# atmega_breakout.net
KiCad netlist of a schematic drawn in EAGLE
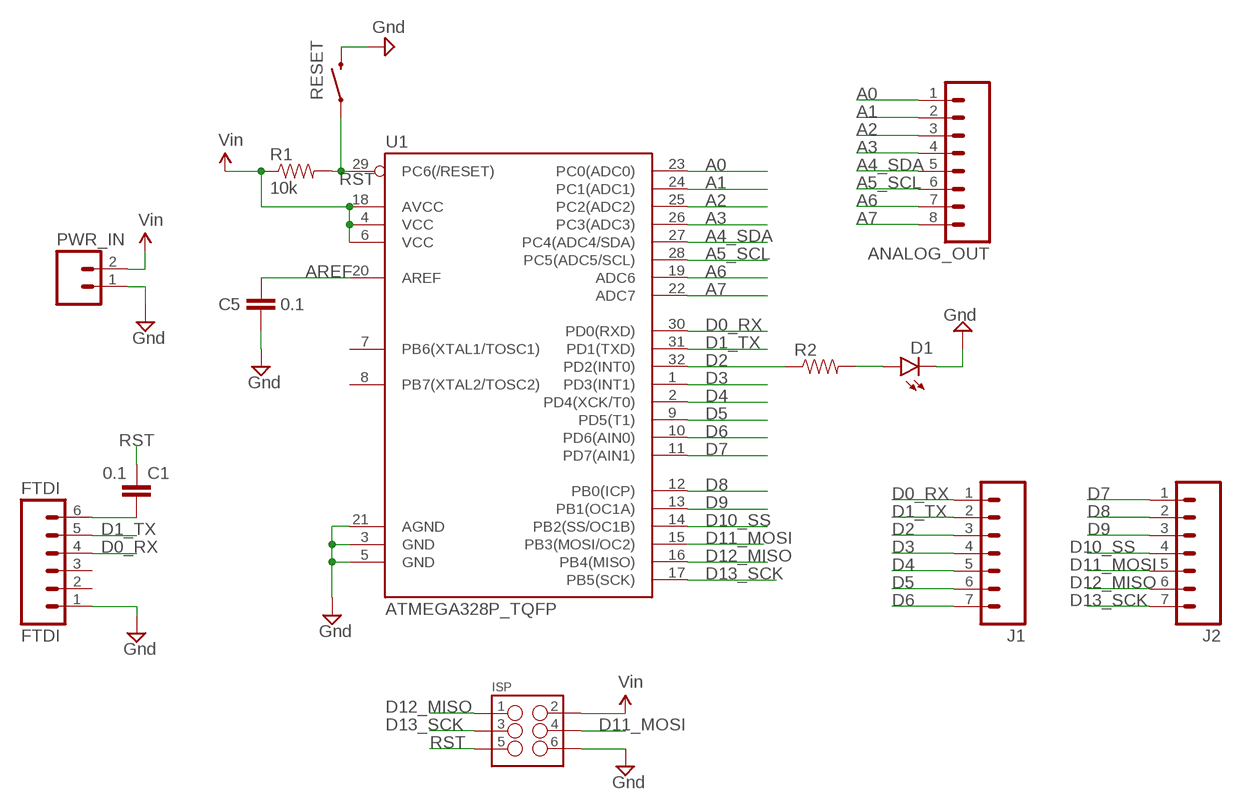
[diagram p0: schematic, sheet 1]

(export (version "E")
  (design (tool "Eeschema 10.0.6"))
  (components
    (comp (ref "ANALOG_OUT")
      (value "M08")
      (footprint "eagle-import:1X08_ROUND")
      (libsource (lib "eagle-import") (part "M08"))
    )
    (comp (ref "C1")
      (value "0.1")
      (footprint "eagle-import:1206")
      (libsource (lib "eagle-import") (part "SparkFun-Passives_CAP1206"))
    )
    (comp (ref "C5")
      (value "0.1")
      (footprint "eagle-import:1206")
      (libsource (lib "eagle-import") (part "CAP1206"))
    )
    (comp (ref "D1")
      (value "LED1206")
      (footprint "eagle-import:LED-1206")
      (libsource (lib "eagle-import") (part "LED1206"))
    )
    (comp (ref "FTDI")
      (value "FTDI")
      (footprint "eagle-import:1X06")
      (libsource (lib "eagle-import") (part "M06SIP"))
    )
    (comp (ref "ISP")
      (value "M03X22X3_SILK_MALE_PTH")
      (footprint "eagle-import:2X3")
      (libsource (lib "eagle-import") (part "M03X22X3_SILK_MALE_PTH"))
    )
    (comp (ref "J1")
      (value "M07")
      (footprint "eagle-import:1X07")
      (libsource (lib "eagle-import") (part "M07"))
    )
    (comp (ref "J2")
      (value "M07")
      (footprint "eagle-import:1X07")
      (libsource (lib "eagle-import") (part "M07"))
    )
    (comp (ref "PWR_IN")
      (value "M02PTH")
      (footprint "eagle-import:1X02")
      (libsource (lib "eagle-import") (part "M02PTH"))
    )
    (comp (ref "R1")
      (value "10k")
      (footprint "eagle-import:1206")
      (libsource (lib "eagle-import") (part "RESISTOR1206"))
    )
    (comp (ref "R2")
      (value "RESISTOR1206")
      (footprint "eagle-import:1206")
      (libsource (lib "eagle-import") (part "RESISTOR1206"))
    )
    (comp (ref "RESET")
      (value "SWITCH-MOMENTARY-2SMD")
      (footprint "eagle-import:TACTILE-SWITCH-SMD")
      (libsource (lib "eagle-import") (part "SWITCH-MOMENTARY-2SMD"))
    )
    (comp (ref "U1")
      (value "ATMEGA328P_TQFP")
      (footprint "eagle-import:TQFP32-08")
      (libsource (lib "eagle-import") (part "ATMEGA328P_TQFP"))
    )
  )
  (nets
    (net (code "1") (name "/A0") (class "Default")
      (node (ref "ANALOG_OUT") (pin "1") (pinfunction "1_1") (pintype "passive"))
      (node (ref "U1") (pin "23") (pinfunction "PC0(ADC0)_23") (pintype "bidirectional"))
    )
    (net (code "2") (name "/A1") (class "Default")
      (node (ref "ANALOG_OUT") (pin "2") (pinfunction "2_2") (pintype "passive"))
      (node (ref "U1") (pin "24") (pinfunction "PC1(ADC1)_24") (pintype "bidirectional"))
    )
    (net (code "3") (name "/A2") (class "Default")
      (node (ref "ANALOG_OUT") (pin "3") (pinfunction "3_3") (pintype "passive"))
      (node (ref "U1") (pin "25") (pinfunction "PC2(ADC2)_25") (pintype "bidirectional"))
    )
    (net (code "4") (name "/A3") (class "Default")
      (node (ref "ANALOG_OUT") (pin "4") (pinfunction "4_4") (pintype "passive"))
      (node (ref "U1") (pin "26") (pinfunction "PC3(ADC3)_26") (pintype "bidirectional"))
    )
    (net (code "5") (name "/A4_SDA") (class "Default")
      (node (ref "ANALOG_OUT") (pin "5") (pinfunction "5_5") (pintype "passive"))
      (node (ref "U1") (pin "27") (pinfunction "PC4(ADC4/SDA)_27") (pintype "bidirectional"))
    )
    (net (code "6") (name "/A5_SCL") (class "Default")
      (node (ref "ANALOG_OUT") (pin "6") (pinfunction "6_6") (pintype "passive"))
      (node (ref "U1") (pin "28") (pinfunction "PC5(ADC5/SCL)_28") (pintype "bidirectional"))
    )
    (net (code "7") (name "/A6") (class "Default")
      (node (ref "ANALOG_OUT") (pin "7") (pinfunction "7_7") (pintype "passive"))
      (node (ref "U1") (pin "19") (pinfunction "ADC6_19") (pintype "bidirectional"))
    )
    (net (code "8") (name "/A7") (class "Default")
      (node (ref "ANALOG_OUT") (pin "8") (pinfunction "8_8") (pintype "passive"))
      (node (ref "U1") (pin "22") (pinfunction "ADC7_22") (pintype "bidirectional"))
    )
    (net (code "9") (name "/AREF") (class "Default")
      (node (ref "C5") (pin "1") (pinfunction "1_1") (pintype "passive"))
      (node (ref "U1") (pin "20") (pinfunction "AREF_20") (pintype "bidirectional"))
    )
    (net (code "10") (name "/D0_RX") (class "Default")
      (node (ref "FTDI") (pin "4") (pinfunction "4_4") (pintype "passive"))
      (node (ref "J1") (pin "1") (pinfunction "1_1") (pintype "passive"))
      (node (ref "U1") (pin "30") (pinfunction "PD0(RXD)_30") (pintype "bidirectional"))
    )
    (net (code "11") (name "/D1_TX") (class "Default")
      (node (ref "FTDI") (pin "5") (pinfunction "5_5") (pintype "passive"))
      (node (ref "J1") (pin "2") (pinfunction "2_2") (pintype "passive"))
      (node (ref "U1") (pin "31") (pinfunction "PD1(TXD)_31") (pintype "bidirectional"))
    )
    (net (code "12") (name "/D2") (class "Default")
      (node (ref "J1") (pin "3") (pinfunction "3_3") (pintype "passive"))
      (node (ref "R2") (pin "1") (pinfunction "1_1") (pintype "passive"))
      (node (ref "U1") (pin "32") (pinfunction "PD2(INT0)_32") (pintype "bidirectional"))
    )
    (net (code "13") (name "/D3") (class "Default")
      (node (ref "J1") (pin "4") (pinfunction "4_4") (pintype "passive"))
      (node (ref "U1") (pin "1") (pinfunction "PD3(INT1)_1") (pintype "bidirectional"))
    )
    (net (code "14") (name "/D4") (class "Default")
      (node (ref "J1") (pin "5") (pinfunction "5_5") (pintype "passive"))
      (node (ref "U1") (pin "2") (pinfunction "PD4(XCK/T0)_2") (pintype "bidirectional"))
    )
    (net (code "15") (name "/D5") (class "Default")
      (node (ref "J1") (pin "6") (pinfunction "6_6") (pintype "passive"))
      (node (ref "U1") (pin "9") (pinfunction "PD5(T1)_9") (pintype "bidirectional"))
    )
    (net (code "16") (name "/D6") (class "Default")
      (node (ref "J1") (pin "7") (pinfunction "7_7") (pintype "passive"))
      (node (ref "U1") (pin "10") (pinfunction "PD6(AIN0)_10") (pintype "bidirectional"))
    )
    (net (code "17") (name "/D7") (class "Default")
      (node (ref "J2") (pin "1") (pinfunction "1_1") (pintype "passive"))
      (node (ref "U1") (pin "11") (pinfunction "PD7(AIN1)_11") (pintype "bidirectional"))
    )
    (net (code "18") (name "/D8") (class "Default")
      (node (ref "J2") (pin "2") (pinfunction "2_2") (pintype "passive"))
      (node (ref "U1") (pin "12") (pinfunction "PB0(ICP)_12") (pintype "bidirectional"))
    )
    (net (code "19") (name "/D9") (class "Default")
      (node (ref "J2") (pin "3") (pinfunction "3_3") (pintype "passive"))
      (node (ref "U1") (pin "13") (pinfunction "PB1(OC1A)_13") (pintype "bidirectional"))
    )
    (net (code "20") (name "/D10_SS") (class "Default")
      (node (ref "J2") (pin "4") (pinfunction "4_4") (pintype "passive"))
      (node (ref "U1") (pin "14") (pinfunction "PB2(SS/OC1B)_14") (pintype "bidirectional"))
    )
    (net (code "21") (name "/D11_MOSI") (class "Default")
      (node (ref "ISP") (pin "4") (pinfunction "4_4") (pintype "bidirectional"))
      (node (ref "J2") (pin "5") (pinfunction "5_5") (pintype "passive"))
      (node (ref "U1") (pin "15") (pinfunction "PB3(MOSI/OC2)_15") (pintype "bidirectional"))
    )
    (net (code "22") (name "/D12_MISO") (class "Default")
      (node (ref "ISP") (pin "1") (pinfunction "1_1") (pintype "bidirectional"))
      (node (ref "J2") (pin "6") (pinfunction "6_6") (pintype "passive"))
      (node (ref "U1") (pin "16") (pinfunction "PB4(MISO)_16") (pintype "bidirectional"))
    )
    (net (code "23") (name "/D13_SCK") (class "Default")
      (node (ref "ISP") (pin "3") (pinfunction "3_3") (pintype "bidirectional"))
      (node (ref "J2") (pin "7") (pinfunction "7_7") (pintype "passive"))
      (node (ref "U1") (pin "17") (pinfunction "PB5(SCK)_17") (pintype "bidirectional"))
    )
    (net (code "24") (name "/RST") (class "Default")
      (node (ref "C1") (pin "1") (pinfunction "1_1") (pintype "passive"))
      (node (ref "ISP") (pin "5") (pinfunction "5_5") (pintype "bidirectional"))
      (node (ref "R1") (pin "2") (pinfunction "2_2") (pintype "passive"))
      (node (ref "RESET") (pin "1") (pinfunction "1_1") (pintype "passive"))
      (node (ref "U1") (pin "29") (pinfunction "PC6(/RESET)_29") (pintype "bidirectional"))
    )
    (net (code "25") (name "Gnd") (class "Default")
      (node (ref "C5") (pin "2") (pinfunction "2_2") (pintype "passive"))
      (node (ref "D1") (pin "C") (pinfunction "C_C") (pintype "passive"))
      (node (ref "FTDI") (pin "1") (pinfunction "1_1") (pintype "passive"))
      (node (ref "ISP") (pin "6") (pinfunction "6_6") (pintype "bidirectional"))
      (node (ref "PWR_IN") (pin "1") (pinfunction "1_1") (pintype "passive"))
      (node (ref "RESET") (pin "3") (pinfunction "2_3") (pintype "passive"))
      (node (ref "U1") (pin "21") (pinfunction "AGND_21") (pintype "bidirectional"))
      (node (ref "U1") (pin "3") (pinfunction "GND_3") (pintype "bidirectional"))
      (node (ref "U1") (pin "5") (pinfunction "GND_5") (pintype "bidirectional"))
    )
    (net (code "26") (name "Net-(C1-Pad2)") (class "Default")
      (node (ref "C1") (pin "2") (pinfunction "2_2") (pintype "passive"))
      (node (ref "FTDI") (pin "6") (pinfunction "6_6") (pintype "passive"))
    )
    (net (code "27") (name "Net-(D1-PadA)") (class "Default")
      (node (ref "D1") (pin "A") (pinfunction "A_A") (pintype "passive"))
      (node (ref "R2") (pin "2") (pinfunction "2_2") (pintype "passive"))
    )
    (net (code "28") (name "Vin") (class "Default")
      (node (ref "ISP") (pin "2") (pinfunction "2_2") (pintype "bidirectional"))
      (node (ref "PWR_IN") (pin "2") (pinfunction "2_2") (pintype "passive"))
      (node (ref "R1") (pin "1") (pinfunction "1_1") (pintype "passive"))
      (node (ref "U1") (pin "18") (pinfunction "AVCC_18") (pintype "bidirectional"))
      (node (ref "U1") (pin "4") (pinfunction "VCC_4") (pintype "bidirectional"))
      (node (ref "U1") (pin "6") (pinfunction "VCC_6") (pintype "bidirectional"))
    )
    (net (code "29") (name "unconnected-(FTDI-Pad2)") (class "Default")
      (node (ref "FTDI") (pin "2") (pinfunction "2_2") (pintype "passive"))
    )
    (net (code "30") (name "unconnected-(FTDI-Pad3)") (class "Default")
      (node (ref "FTDI") (pin "3") (pinfunction "3_3") (pintype "passive"))
    )
    (net (code "31") (name "unconnected-(U1-PB6(XTAL1{slash}TOSC1)-Pad7)") (class "Default")
      (node (ref "U1") (pin "7") (pinfunction "PB6(XTAL1/TOSC1)_7") (pintype "bidirectional"))
    )
    (net (code "32") (name "unconnected-(U1-PB7(XTAL2{slash}TOSC2)-Pad8)") (class "Default")
      (node (ref "U1") (pin "8") (pinfunction "PB7(XTAL2/TOSC2)_8") (pintype "bidirectional"))
    )
  )
)
